# alimentation.net
KiCad netlist of a schematic drawn in Altium Designer
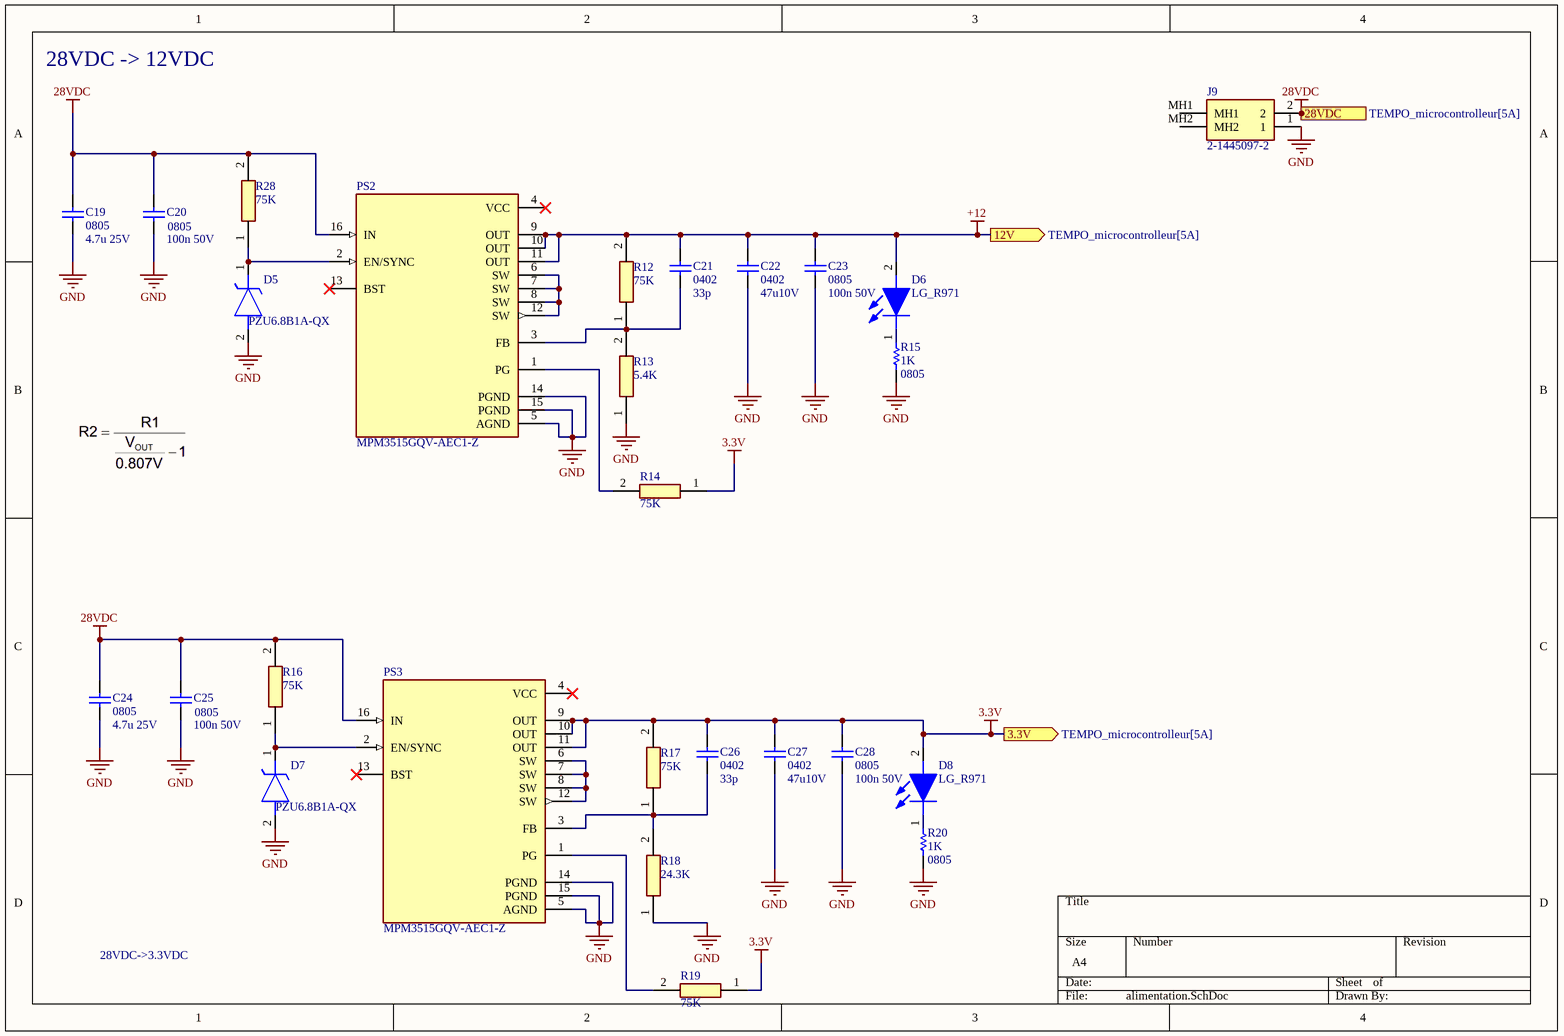
[diagram p0: alimentation.SchDoc]

(export (version "E")
  (design (tool "Eeschema 10.0.6"))
  (components
    (comp (ref "C19")
      (value "4.7u 25V")
      (footprint "CONDENSATEUR_CMS_0805")
      (description "CONDENSATEUR CMS CERAMIQUE 0805")
      (fields (field (name "TYPE") "0805") (field (name "Comment") "CMS_0805"))
      (libsource (lib "composants passifs") (part "CONDENSATEUR_CMS_CER_0805"))
    )
    (comp (ref "C20")
      (value "100n 50V")
      (footprint "CONDENSATEUR_CMS_0805")
      (description "CONDENSATEUR CMS CERAMIQUE 0805")
      (fields (field (name "TYPE") "0805") (field (name "Comment") "CMS_0805"))
      (libsource (lib "composants passifs") (part "CONDENSATEUR_CMS_CER_0805"))
    )
    (comp (ref "C21")
      (value "33p")
      (footprint "CONDENSATEUR_CMS_0402")
      (description "CONDENSATEUR CMS CERAMIQUE 0402")
      (fields (field (name "TYPE") "0402") (field (name "Comment") "CMS_0402"))
      (libsource (lib "composants passifs") (part "CONDENSATEUR_CMS_CER_0402"))
    )
    (comp (ref "C22")
      (value "47u10V")
      (footprint "CONDENSATEUR_CMS_0402")
      (description "CONDENSATEUR CMS CERAMIQUE 0402")
      (fields (field (name "TYPE") "0402") (field (name "Comment") "CMS_0402"))
      (libsource (lib "composants passifs") (part "CONDENSATEUR_CMS_CER_0402"))
    )
    (comp (ref "C23")
      (value "100n 50V")
      (footprint "CONDENSATEUR_CMS_0402")
      (description "CONDENSATEUR CMS CERAMIQUE 0402")
      (fields (field (name "TYPE") "0805") (field (name "Comment") "CMS_0402"))
      (libsource (lib "composants passifs") (part "CONDENSATEUR_CMS_CER_0402"))
    )
    (comp (ref "C24")
      (value "4.7u 25V")
      (footprint "CONDENSATEUR_CMS_0805")
      (description "CONDENSATEUR CMS CERAMIQUE 0805")
      (fields (field (name "TYPE") "0805") (field (name "Comment") "CMS_0805"))
      (libsource (lib "composants passifs") (part "CONDENSATEUR_CMS_CER_0805"))
    )
    (comp (ref "C25")
      (value "100n 50V")
      (footprint "CONDENSATEUR_CMS_0805")
      (description "CONDENSATEUR CMS CERAMIQUE 0805")
      (fields (field (name "TYPE") "0805") (field (name "Comment") "CMS_0805"))
      (libsource (lib "composants passifs") (part "CONDENSATEUR_CMS_CER_0805"))
    )
    (comp (ref "C26")
      (value "33p")
      (footprint "CONDENSATEUR_CMS_0402")
      (description "CONDENSATEUR CMS CERAMIQUE 0402")
      (fields (field (name "TYPE") "0402") (field (name "Comment") "CMS_0402"))
      (libsource (lib "composants passifs") (part "CONDENSATEUR_CMS_CER_0402"))
    )
    (comp (ref "C27")
      (value "47u10V")
      (footprint "CONDENSATEUR_CMS_0402")
      (description "CONDENSATEUR CMS CERAMIQUE 0402")
      (fields (field (name "TYPE") "0402") (field (name "Comment") "CMS_0402"))
      (libsource (lib "composants passifs") (part "CONDENSATEUR_CMS_CER_0402"))
    )
    (comp (ref "C28")
      (value "100n 50V")
      (footprint "CONDENSATEUR_CMS_0402")
      (description "CONDENSATEUR CMS CERAMIQUE 0402")
      (fields (field (name "TYPE") "0805") (field (name "Comment") "CMS_0402"))
      (libsource (lib "composants passifs") (part "CONDENSATEUR_CMS_CER_0402"))
    )
    (comp (ref "D5")
      (value "PZU6.8B1A-QX")
      (footprint "SamacSys:PZU68B1AQX")
      (description "Zener Diode")
      (libsource (lib "*") (part "PZU6.8B1A-QX"))
    )
    (comp (ref "D6")
      (value "LG_R971")
      (footprint "LEDC2012X90N")
      (description "Green 570nm LED Indication - Discrete 2.2V 0805 (2012 Metric)")
      (fields (field (name "MF") "OSRAM Opto") (field (name "MP") "LG R971"))
      (libsource (lib "LG_R971") (part "LG_R971"))
    )
    (comp (ref "D7")
      (value "PZU6.8B1A-QX")
      (footprint "SamacSys:PZU68B1AQX")
      (description "Zener Diode")
      (libsource (lib "*") (part "PZU6.8B1A-QX"))
    )
    (comp (ref "D8")
      (value "LG_R971")
      (footprint "LEDC2012X90N")
      (description "Green 570nm LED Indication - Discrete 2.2V 0805 (2012 Metric)")
      (fields (field (name "MF") "OSRAM Opto") (field (name "MP") "LG R971"))
      (libsource (lib "LG_R971") (part "LG_R971"))
    )
    (comp (ref "J9")
      (value "2-1445097-2")
      (footprint "214450972")
      (description "MICRO MNL HDR ASSY S/ROW AU LF")
      (fields (field (name "MOUSER PART NUMBER") "571-2-1445097-2"))
      (libsource (lib "2-1445097-2") (part "2-1445097-2"))
    )
    (comp (ref "PS2")
      (value "MPM3515GQV-AEC1-Z")
      (footprint "CONV_MPM3515GQV-AEC1-Z")
      (description "Non-Isolated PoL Module DC DC Converter 1 Output 0.8 ~ 30V 1.5A 4V - 36V Input")
      (fields (field (name "MF") "Monolithic Power"))
      (libsource (lib "MPM3515GQV-AEC1-Z") (part "MPM3515GQV-AEC1-Z"))
    )
    (comp (ref "PS3")
      (value "MPM3515GQV-AEC1-Z")
      (footprint "CONV_MPM3515GQV-AEC1-Z")
      (description "Non-Isolated PoL Module DC DC Converter 1 Output 0.8 ~ 30V 1.5A 4V - 36V Input")
      (fields (field (name "MF") "Monolithic Power"))
      (libsource (lib "MPM3515GQV-AEC1-Z") (part "MPM3515GQV-AEC1-Z"))
    )
    (comp (ref "R12")
      (value "75K")
      (footprint "214450973:RESC1005X40N")
      (description "Resistor")
      (fields
        (field (name "RS PART NUMBER") "2508364793")
        (field (name "MANUFACTURER_PART_NUMBER") "CRCW04020000Z0ED")
      )
      (libsource (lib "2-1445097-3") (part "CRCW04020000Z0ED"))
    )
    (comp (ref "R13")
      (value "5.4K")
      (footprint "214450973:RESC1005X40N")
      (description "Resistor")
      (fields
        (field (name "RS PART NUMBER") "2508364793")
        (field (name "MANUFACTURER_PART_NUMBER") "CRCW04020000Z0ED")
      )
      (libsource (lib "2-1445097-3") (part "CRCW04020000Z0ED"))
    )
    (comp (ref "R14")
      (value "75K")
      (footprint "214450973:RESC1005X40N")
      (description "Resistor")
      (fields
        (field (name "RS PART NUMBER") "2508364793")
        (field (name "MANUFACTURER_PART_NUMBER") "CRCW04020000Z0ED")
      )
      (libsource (lib "") (part "CRCW04020000Z0ED_1"))
    )
    (comp (ref "R15")
      (value "1K")
      (footprint "RESISTANCE_CMS_0603")
      (description "RESISTANCE CMS 0603")
      (fields (field (name "TYPE") "0805") (field (name "Comment") "RESISTANCE_CMS_0603"))
      (libsource (lib "composants passifs") (part "RESISTANCE_CMS_0603"))
    )
    (comp (ref "R16")
      (value "75K")
      (footprint "214450973:RESC1005X40N")
      (description "Resistor")
      (fields
        (field (name "RS PART NUMBER") "2508364793")
        (field (name "MANUFACTURER_PART_NUMBER") "CRCW04020000Z0ED")
      )
      (libsource (lib "2-1445097-3") (part "CRCW04020000Z0ED"))
    )
    (comp (ref "R17")
      (value "75K")
      (footprint "214450973:RESC1005X40N")
      (description "Resistor")
      (fields
        (field (name "RS PART NUMBER") "2508364793")
        (field (name "MANUFACTURER_PART_NUMBER") "CRCW04020000Z0ED")
      )
      (libsource (lib "2-1445097-3") (part "CRCW04020000Z0ED"))
    )
    (comp (ref "R18")
      (value "24.3K")
      (footprint "214450973:RESC1005X40N")
      (description "Resistor")
      (fields
        (field (name "RS PART NUMBER") "2508364793")
        (field (name "MANUFACTURER_PART_NUMBER") "CRCW04020000Z0ED")
      )
      (libsource (lib "2-1445097-3") (part "CRCW04020000Z0ED"))
    )
    (comp (ref "R19")
      (value "75K")
      (footprint "214450973:RESC1005X40N")
      (description "Resistor")
      (fields
        (field (name "RS PART NUMBER") "2508364793")
        (field (name "MANUFACTURER_PART_NUMBER") "CRCW04020000Z0ED")
      )
      (libsource (lib "") (part "CRCW04020000Z0ED_1"))
    )
    (comp (ref "R20")
      (value "1K")
      (footprint "RESISTANCE_CMS_0603")
      (description "RESISTANCE CMS 0603")
      (fields (field (name "TYPE") "0805") (field (name "Comment") "RESISTANCE_CMS_0603"))
      (libsource (lib "composants passifs") (part "RESISTANCE_CMS_0603"))
    )
    (comp (ref "R28")
      (value "75K")
      (footprint "214450973:RESC1005X40N")
      (description "Resistor")
      (fields
        (field (name "RS PART NUMBER") "2508364793")
        (field (name "MANUFACTURER_PART_NUMBER") "CRCW04020000Z0ED")
      )
      (libsource (lib "2-1445097-3") (part "CRCW04020000Z0ED"))
    )
  )
  (nets
    (net (code "1") (name "+12") (class "Default")
      (node (ref "C21") (pin "1") (pinfunction "1_1") (pintype "passive"))
      (node (ref "C22") (pin "1") (pinfunction "1_1") (pintype "passive"))
      (node (ref "C23") (pin "1") (pinfunction "1_1") (pintype "passive"))
      (node (ref "D6") (pin "2") (pinfunction "A_2") (pintype "passive"))
      (node (ref "PS2") (pin "10") (pinfunction "OUT_10") (pintype "passive"))
      (node (ref "PS2") (pin "11") (pinfunction "OUT_11") (pintype "passive"))
      (node (ref "PS2") (pin "9") (pinfunction "OUT_9") (pintype "passive"))
      (node (ref "R12") (pin "2") (pinfunction "2_2") (pintype "passive"))
    )
    (net (code "2") (name "3.3V") (class "Default")
      (node (ref "C26") (pin "1") (pinfunction "1_1") (pintype "passive"))
      (node (ref "C27") (pin "1") (pinfunction "1_1") (pintype "passive"))
      (node (ref "C28") (pin "1") (pinfunction "1_1") (pintype "passive"))
      (node (ref "D8") (pin "2") (pinfunction "A_2") (pintype "passive"))
      (node (ref "PS3") (pin "10") (pinfunction "OUT_10") (pintype "passive"))
      (node (ref "PS3") (pin "11") (pinfunction "OUT_11") (pintype "passive"))
      (node (ref "PS3") (pin "9") (pinfunction "OUT_9") (pintype "passive"))
      (node (ref "R14") (pin "1") (pinfunction "1_1") (pintype "passive"))
      (node (ref "R17") (pin "2") (pinfunction "2_2") (pintype "passive"))
      (node (ref "R19") (pin "1") (pinfunction "1_1") (pintype "passive"))
    )
    (net (code "3") (name "28VDC") (class "Default")
      (node (ref "C19") (pin "2") (pinfunction "2_2") (pintype "passive"))
      (node (ref "C20") (pin "2") (pinfunction "2_2") (pintype "passive"))
      (node (ref "C24") (pin "2") (pinfunction "2_2") (pintype "passive"))
      (node (ref "C25") (pin "2") (pinfunction "2_2") (pintype "passive"))
      (node (ref "J9") (pin "2") (pinfunction "2_2") (pintype "passive"))
      (node (ref "PS2") (pin "16") (pinfunction "IN_16") (pintype "input"))
      (node (ref "PS3") (pin "16") (pinfunction "IN_16") (pintype "input"))
      (node (ref "R16") (pin "2") (pinfunction "2_2") (pintype "passive"))
      (node (ref "R28") (pin "2") (pinfunction "2_2") (pintype "passive"))
    )
    (net (code "4") (name "GND") (class "Default")
      (node (ref "C19") (pin "1") (pinfunction "1_1") (pintype "passive"))
      (node (ref "C20") (pin "1") (pinfunction "1_1") (pintype "passive"))
      (node (ref "C22") (pin "2") (pinfunction "2_2") (pintype "passive"))
      (node (ref "C23") (pin "2") (pinfunction "2_2") (pintype "passive"))
      (node (ref "C24") (pin "1") (pinfunction "1_1") (pintype "passive"))
      (node (ref "C25") (pin "1") (pinfunction "1_1") (pintype "passive"))
      (node (ref "C27") (pin "2") (pinfunction "2_2") (pintype "passive"))
      (node (ref "C28") (pin "2") (pinfunction "2_2") (pintype "passive"))
      (node (ref "D5") (pin "2") (pinfunction "A_2") (pintype "passive"))
      (node (ref "D7") (pin "2") (pinfunction "A_2") (pintype "passive"))
      (node (ref "J9") (pin "1") (pinfunction "1_1") (pintype "passive"))
      (node (ref "PS2") (pin "14") (pinfunction "PGND_14") (pintype "power_in"))
      (node (ref "PS2") (pin "15") (pinfunction "PGND_15") (pintype "power_in"))
      (node (ref "PS2") (pin "5") (pinfunction "AGND_5") (pintype "passive"))
      (node (ref "PS3") (pin "14") (pinfunction "PGND_14") (pintype "power_in"))
      (node (ref "PS3") (pin "15") (pinfunction "PGND_15") (pintype "power_in"))
      (node (ref "PS3") (pin "5") (pinfunction "AGND_5") (pintype "passive"))
      (node (ref "R13") (pin "1") (pinfunction "1_1") (pintype "passive"))
      (node (ref "R15") (pin "1") (pinfunction "1_1") (pintype "passive"))
      (node (ref "R18") (pin "1") (pinfunction "1_1") (pintype "passive"))
      (node (ref "R20") (pin "1") (pinfunction "1_1") (pintype "passive"))
    )
    (net (code "5") (name "Net-(D5-K)") (class "Default")
      (node (ref "D5") (pin "1") (pinfunction "K_1") (pintype "passive"))
      (node (ref "PS2") (pin "2") (pinfunction "EN/SYNC_2") (pintype "input"))
      (node (ref "R28") (pin "1") (pinfunction "1_1") (pintype "passive"))
    )
    (net (code "6") (name "Net-(D6-K)") (class "Default")
      (node (ref "D6") (pin "1") (pinfunction "K_1") (pintype "passive"))
      (node (ref "R15") (pin "2") (pinfunction "2_2") (pintype "passive"))
    )
    (net (code "7") (name "Net-(D7-K)") (class "Default")
      (node (ref "D7") (pin "1") (pinfunction "K_1") (pintype "passive"))
      (node (ref "PS3") (pin "2") (pinfunction "EN/SYNC_2") (pintype "input"))
      (node (ref "R16") (pin "1") (pinfunction "1_1") (pintype "passive"))
    )
    (net (code "8") (name "Net-(D8-K)") (class "Default")
      (node (ref "D8") (pin "1") (pinfunction "K_1") (pintype "passive"))
      (node (ref "R20") (pin "2") (pinfunction "2_2") (pintype "passive"))
    )
    (net (code "9") (name "Net-(PS2-FB)") (class "Default")
      (node (ref "C21") (pin "2") (pinfunction "2_2") (pintype "passive"))
      (node (ref "PS2") (pin "3") (pinfunction "FB_3") (pintype "passive"))
      (node (ref "R12") (pin "1") (pinfunction "1_1") (pintype "passive"))
      (node (ref "R13") (pin "2") (pinfunction "2_2") (pintype "passive"))
    )
    (net (code "10") (name "Net-(PS2-PG)") (class "Default")
      (node (ref "PS2") (pin "1") (pinfunction "PG_1") (pintype "passive"))
      (node (ref "R14") (pin "2") (pinfunction "2_2") (pintype "passive"))
    )
    (net (code "11") (name "Net-(PS2-SW-Pad12)") (class "Default")
      (node (ref "PS2") (pin "12") (pinfunction "SW_12") (pintype "output"))
      (node (ref "PS2") (pin "6") (pinfunction "SW_6") (pintype "passive"))
      (node (ref "PS2") (pin "7") (pinfunction "SW_7") (pintype "passive"))
      (node (ref "PS2") (pin "8") (pinfunction "SW_8") (pintype "passive"))
    )
    (net (code "12") (name "Net-(PS3-FB)") (class "Default")
      (node (ref "C26") (pin "2") (pinfunction "2_2") (pintype "passive"))
      (node (ref "PS3") (pin "3") (pinfunction "FB_3") (pintype "passive"))
      (node (ref "R17") (pin "1") (pinfunction "1_1") (pintype "passive"))
      (node (ref "R18") (pin "2") (pinfunction "2_2") (pintype "passive"))
    )
    (net (code "13") (name "Net-(PS3-PG)") (class "Default")
      (node (ref "PS3") (pin "1") (pinfunction "PG_1") (pintype "passive"))
      (node (ref "R19") (pin "2") (pinfunction "2_2") (pintype "passive"))
    )
    (net (code "14") (name "Net-(PS3-SW-Pad12)") (class "Default")
      (node (ref "PS3") (pin "12") (pinfunction "SW_12") (pintype "output"))
      (node (ref "PS3") (pin "6") (pinfunction "SW_6") (pintype "passive"))
      (node (ref "PS3") (pin "7") (pinfunction "SW_7") (pintype "passive"))
      (node (ref "PS3") (pin "8") (pinfunction "SW_8") (pintype "passive"))
    )
    (net (code "15") (name "unconnected-(J9-PadMH1)") (class "Default")
      (node (ref "J9") (pin "MH1") (pinfunction "MH1_MH1") (pintype "passive"))
    )
    (net (code "16") (name "unconnected-(J9-PadMH2)") (class "Default")
      (node (ref "J9") (pin "MH2") (pinfunction "MH2_MH2") (pintype "passive"))
    )
    (net (code "17") (name "unconnected-(PS2-BST-Pad13)") (class "Default")
      (node (ref "PS2") (pin "13") (pinfunction "BST_13") (pintype "passive+no_connect"))
    )
    (net (code "18") (name "unconnected-(PS2-VCC-Pad4)") (class "Default")
      (node (ref "PS2") (pin "4") (pinfunction "VCC_4") (pintype "power_in+no_connect"))
    )
    (net (code "19") (name "unconnected-(PS3-BST-Pad13)") (class "Default")
      (node (ref "PS3") (pin "13") (pinfunction "BST_13") (pintype "passive+no_connect"))
    )
    (net (code "20") (name "unconnected-(PS3-VCC-Pad4)") (class "Default")
      (node (ref "PS3") (pin "4") (pinfunction "VCC_4") (pintype "power_in+no_connect"))
    )
  )
)
